# Dual_VCLFO_CTRL.net
KiCad netlist of a schematic drawn in EAGLE
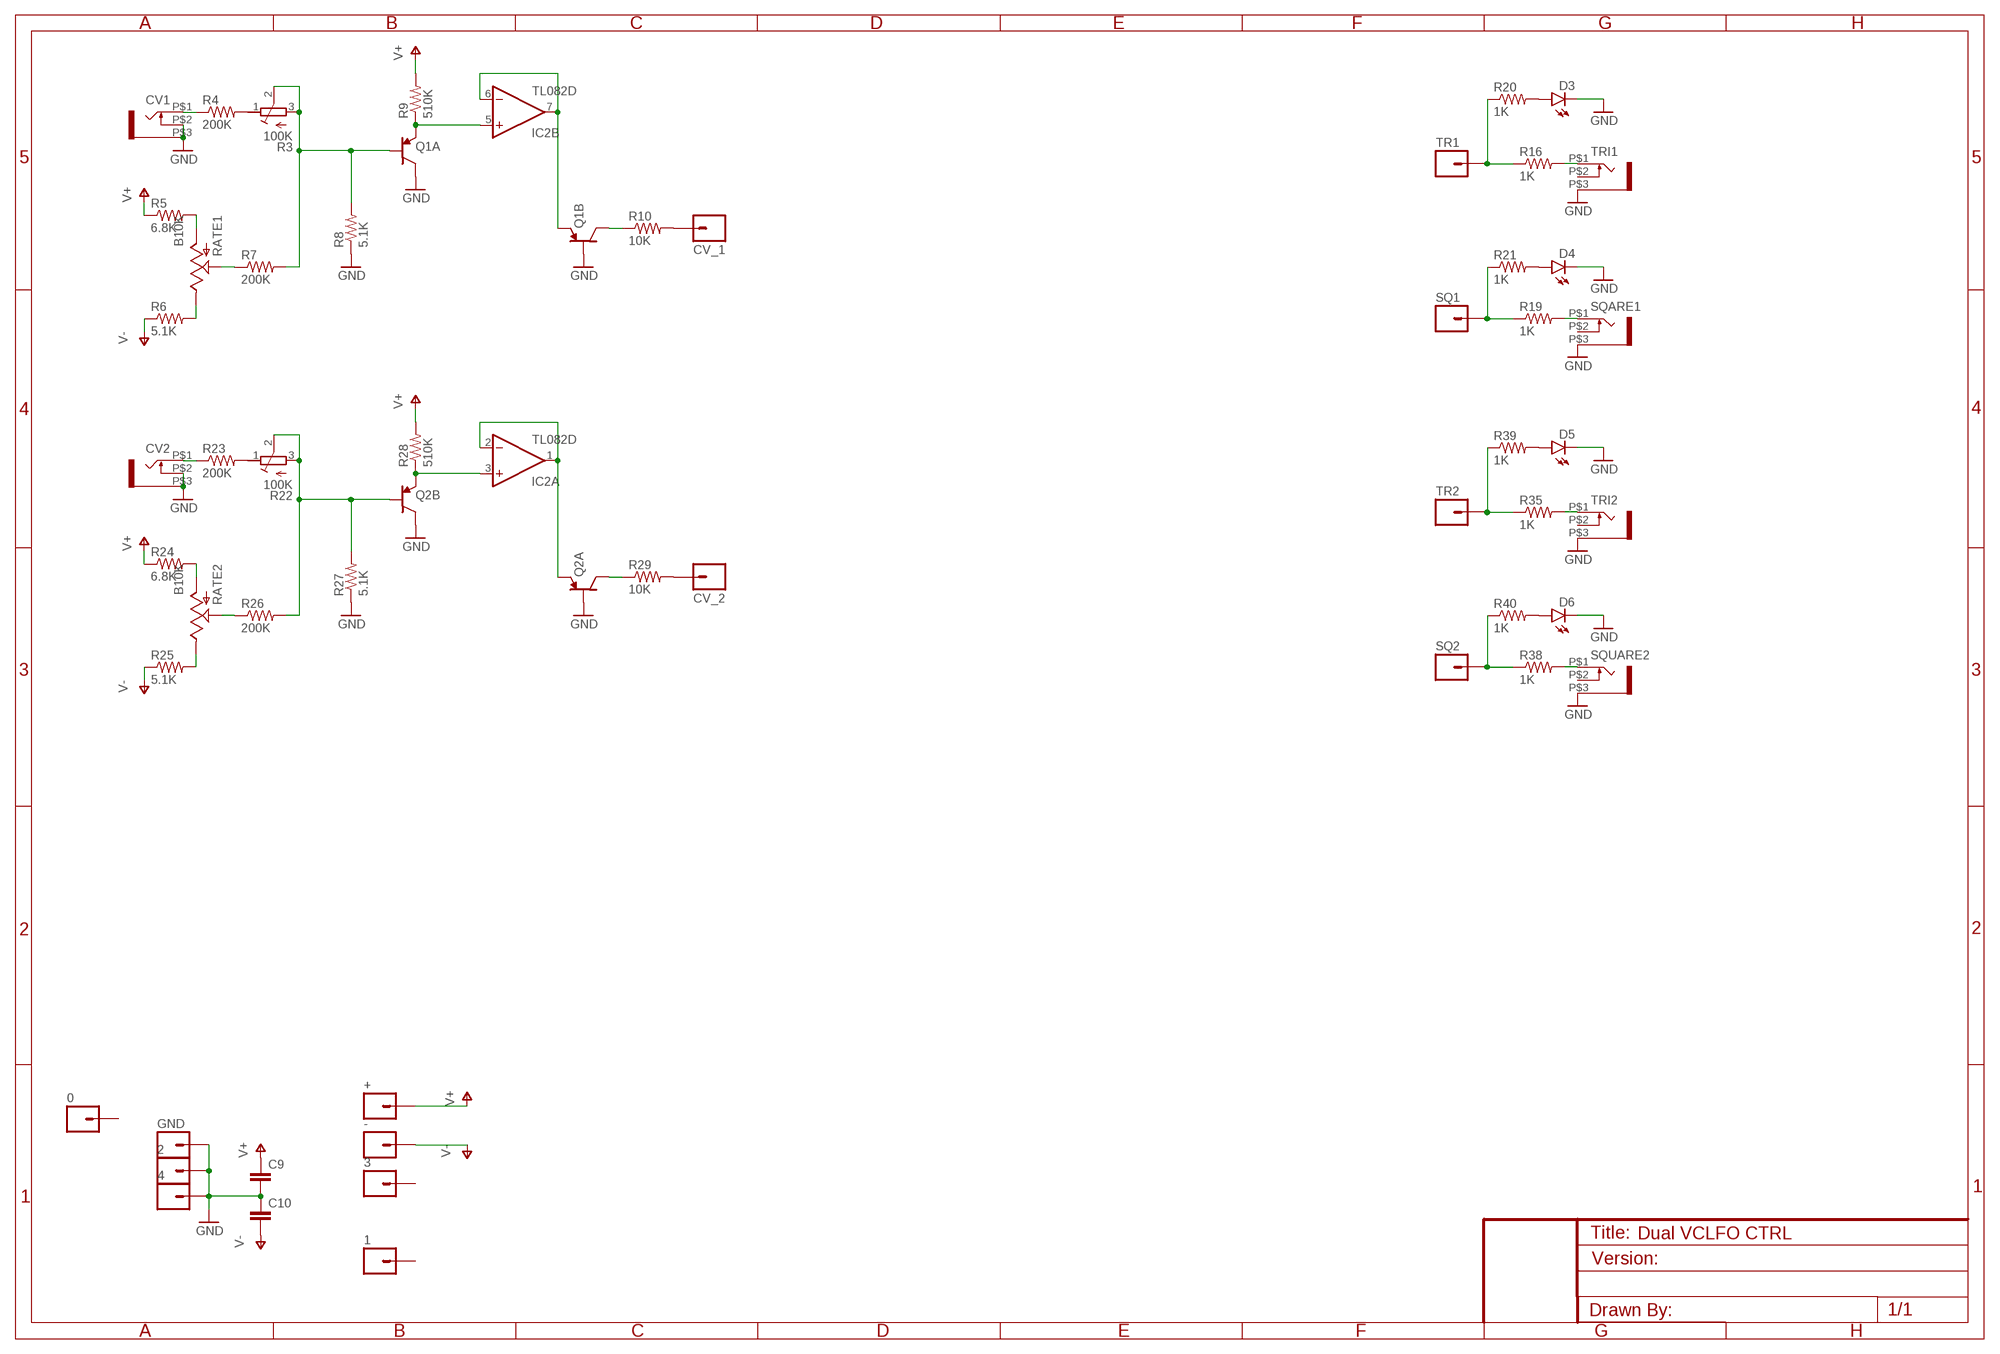
[diagram p0: schematic, sheet 1]

(export (version "E")
  (design (tool "Eeschema 10.0.6"))
  (components
    (comp (ref "+")
      (value "M01PTH")
      (footprint "eagle-import:1X01")
      (libsource (lib "eagle-import") (part "M01PTH"))
    )
    (comp (ref "-")
      (value "M01PTH")
      (footprint "eagle-import:1X01")
      (libsource (lib "eagle-import") (part "M01PTH"))
    )
    (comp (ref "0")
      (value "M01PTH")
      (footprint "eagle-import:1X01")
      (libsource (lib "eagle-import") (part "M01PTH"))
    )
    (comp (ref "1")
      (value "M01PTH")
      (footprint "eagle-import:1X01")
      (libsource (lib "eagle-import") (part "M01PTH"))
    )
    (comp (ref "2")
      (value "M01PTH")
      (footprint "eagle-import:1X01")
      (libsource (lib "eagle-import") (part "M01PTH"))
    )
    (comp (ref "3")
      (value "M01PTH")
      (footprint "eagle-import:1X01")
      (libsource (lib "eagle-import") (part "M01PTH"))
    )
    (comp (ref "4")
      (value "M01PTH")
      (footprint "eagle-import:1X01")
      (libsource (lib "eagle-import") (part "M01PTH"))
    )
    (comp (ref "C9")
      (value "CAP0805")
      (footprint "eagle-import:0805")
      (libsource (lib "eagle-import") (part "CAP0805"))
    )
    (comp (ref "C10")
      (value "CAP0805")
      (footprint "eagle-import:0805")
      (libsource (lib "eagle-import") (part "CAP0805"))
    )
    (comp (ref "CV1")
      (value "WQP-PJ301M-12_JACK")
      (footprint "eagle-import:WQP-PJ301M-12_JACK")
      (libsource (lib "eagle-import") (part "WQP-PJ301M-12_JACK"))
    )
    (comp (ref "CV2")
      (value "WQP-PJ301M-12_JACK")
      (footprint "eagle-import:WQP-PJ301M-12_JACK")
      (libsource (lib "eagle-import") (part "WQP-PJ301M-12_JACK"))
    )
    (comp (ref "CV_1")
      (value "M01PTH")
      (footprint "eagle-import:1X01")
      (libsource (lib "eagle-import") (part "M01PTH"))
    )
    (comp (ref "CV_2")
      (value "M01PTH")
      (footprint "eagle-import:1X01")
      (libsource (lib "eagle-import") (part "M01PTH"))
    )
    (comp (ref "D3")
      (value "LED3MM")
      (footprint "eagle-import:LED3MM")
      (libsource (lib "eagle-import") (part "LED3MM"))
    )
    (comp (ref "D4")
      (value "LED3MM")
      (footprint "eagle-import:LED3MM")
      (libsource (lib "eagle-import") (part "LED3MM"))
    )
    (comp (ref "D5")
      (value "LED3MM")
      (footprint "eagle-import:LED3MM")
      (libsource (lib "eagle-import") (part "LED3MM"))
    )
    (comp (ref "D6")
      (value "LED3MM")
      (footprint "eagle-import:LED3MM")
      (libsource (lib "eagle-import") (part "LED3MM"))
    )
    (comp (ref "GND")
      (value "M01PTH")
      (footprint "eagle-import:1X01")
      (libsource (lib "eagle-import") (part "M01PTH"))
    )
    (comp (ref "IC2")
      (value "TL082D")
      (footprint "eagle-import:SO08")
      (libsource (lib "eagle-import") (part "TL082D"))
    )
    (comp (ref "Q1")
      (value "PNP-DUALPMP5201")
      (footprint "eagle-import:SOT363")
      (libsource (lib "eagle-import") (part "PNP-DUALPMP5201"))
    )
    (comp (ref "Q2")
      (value "PNP-DUALPMP5201")
      (footprint "eagle-import:SOT363")
      (libsource (lib "eagle-import") (part "PNP-DUALPMP5201"))
    )
    (comp (ref "R3")
      (value "100K")
      (footprint "eagle-import:RTRIM3314G")
      (libsource (lib "eagle-import") (part "R-TRIMM3314G"))
    )
    (comp (ref "R4")
      (value "200K")
      (footprint "eagle-import:0805")
      (libsource (lib "eagle-import") (part "RESISTOR0805-RES"))
    )
    (comp (ref "R5")
      (value "6.8K")
      (footprint "eagle-import:0805")
      (libsource (lib "eagle-import") (part "RESISTOR0805-RES"))
    )
    (comp (ref "R6")
      (value "5.1K")
      (footprint "eagle-import:0805")
      (libsource (lib "eagle-import") (part "RESISTOR0805-RES"))
    )
    (comp (ref "R7")
      (value "200K")
      (footprint "eagle-import:0805")
      (libsource (lib "eagle-import") (part "RESISTOR0805-RES"))
    )
    (comp (ref "R8")
      (value "5.1K")
      (footprint "eagle-import:0805")
      (libsource (lib "eagle-import") (part "RESISTOR0805-RES"))
    )
    (comp (ref "R9")
      (value "510K")
      (footprint "eagle-import:0805")
      (libsource (lib "eagle-import") (part "RESISTOR0805-RES"))
    )
    (comp (ref "R10")
      (value "10K")
      (footprint "eagle-import:0805")
      (libsource (lib "eagle-import") (part "RESISTOR0805-RES"))
    )
    (comp (ref "R16")
      (value "1K")
      (footprint "eagle-import:0805")
      (libsource (lib "eagle-import") (part "RESISTOR0805-RES"))
    )
    (comp (ref "R19")
      (value "1K")
      (footprint "eagle-import:0805")
      (libsource (lib "eagle-import") (part "RESISTOR0805-RES"))
    )
    (comp (ref "R20")
      (value "1K")
      (footprint "eagle-import:0805")
      (libsource (lib "eagle-import") (part "RESISTOR0805-RES"))
    )
    (comp (ref "R21")
      (value "1K")
      (footprint "eagle-import:0805")
      (libsource (lib "eagle-import") (part "RESISTOR0805-RES"))
    )
    (comp (ref "R22")
      (value "100K")
      (footprint "eagle-import:RTRIM3314G")
      (libsource (lib "eagle-import") (part "R-TRIMM3314G"))
    )
    (comp (ref "R23")
      (value "200K")
      (footprint "eagle-import:0805")
      (libsource (lib "eagle-import") (part "RESISTOR0805-RES"))
    )
    (comp (ref "R24")
      (value "6.8K")
      (footprint "eagle-import:0805")
      (libsource (lib "eagle-import") (part "RESISTOR0805-RES"))
    )
    (comp (ref "R25")
      (value "5.1K")
      (footprint "eagle-import:0805")
      (libsource (lib "eagle-import") (part "RESISTOR0805-RES"))
    )
    (comp (ref "R26")
      (value "200K")
      (footprint "eagle-import:0805")
      (libsource (lib "eagle-import") (part "RESISTOR0805-RES"))
    )
    (comp (ref "R27")
      (value "5.1K")
      (footprint "eagle-import:0805")
      (libsource (lib "eagle-import") (part "RESISTOR0805-RES"))
    )
    (comp (ref "R28")
      (value "510K")
      (footprint "eagle-import:0805")
      (libsource (lib "eagle-import") (part "RESISTOR0805-RES"))
    )
    (comp (ref "R29")
      (value "10K")
      (footprint "eagle-import:0805")
      (libsource (lib "eagle-import") (part "RESISTOR0805-RES"))
    )
    (comp (ref "R35")
      (value "1K")
      (footprint "eagle-import:0805")
      (libsource (lib "eagle-import") (part "RESISTOR0805-RES"))
    )
    (comp (ref "R38")
      (value "1K")
      (footprint "eagle-import:0805")
      (libsource (lib "eagle-import") (part "RESISTOR0805-RES"))
    )
    (comp (ref "R39")
      (value "1K")
      (footprint "eagle-import:0805")
      (libsource (lib "eagle-import") (part "RESISTOR0805-RES"))
    )
    (comp (ref "R40")
      (value "1K")
      (footprint "eagle-import:0805")
      (libsource (lib "eagle-import") (part "RESISTOR0805-RES"))
    )
    (comp (ref "RATE1")
      (value "B10K")
      (footprint "eagle-import:ALPS_POT")
      (libsource (lib "eagle-import") (part "POT"))
    )
    (comp (ref "RATE2")
      (value "B10K")
      (footprint "eagle-import:ALPS_POT")
      (libsource (lib "eagle-import") (part "POT"))
    )
    (comp (ref "SQ1")
      (value "M01PTH")
      (footprint "eagle-import:1X01")
      (libsource (lib "eagle-import") (part "M01PTH"))
    )
    (comp (ref "SQ2")
      (value "M01PTH")
      (footprint "eagle-import:1X01")
      (libsource (lib "eagle-import") (part "M01PTH"))
    )
    (comp (ref "SQARE1")
      (value "WQP-PJ301M-12_JACK")
      (footprint "eagle-import:WQP-PJ301M-12_JACK")
      (libsource (lib "eagle-import") (part "WQP-PJ301M-12_JACK"))
    )
    (comp (ref "SQUARE2")
      (value "WQP-PJ301M-12_JACK")
      (footprint "eagle-import:WQP-PJ301M-12_JACK")
      (libsource (lib "eagle-import") (part "WQP-PJ301M-12_JACK"))
    )
    (comp (ref "TR1")
      (value "M01PTH")
      (footprint "eagle-import:1X01")
      (libsource (lib "eagle-import") (part "M01PTH"))
    )
    (comp (ref "TR2")
      (value "M01PTH")
      (footprint "eagle-import:1X01")
      (libsource (lib "eagle-import") (part "M01PTH"))
    )
    (comp (ref "TRI1")
      (value "WQP-PJ301M-12_JACK")
      (footprint "eagle-import:WQP-PJ301M-12_JACK")
      (libsource (lib "eagle-import") (part "WQP-PJ301M-12_JACK"))
    )
    (comp (ref "TRI2")
      (value "WQP-PJ301M-12_JACK")
      (footprint "eagle-import:WQP-PJ301M-12_JACK")
      (libsource (lib "eagle-import") (part "WQP-PJ301M-12_JACK"))
    )
  )
  (nets
    (net (code "1") (name "GND") (class "Default")
      (node (ref "2") (pin "1") (pinfunction "1_1") (pintype "passive"))
      (node (ref "4") (pin "1") (pinfunction "1_1") (pintype "passive"))
      (node (ref "C10") (pin "1") (pinfunction "1_1") (pintype "passive"))
      (node (ref "C9") (pin "2") (pinfunction "2_2") (pintype "passive"))
      (node (ref "CV1") (pin "P$2") (pinfunction "3_P$2") (pintype "passive"))
      (node (ref "CV1") (pin "P$3") (pinfunction "1_P$3") (pintype "passive"))
      (node (ref "CV2") (pin "P$2") (pinfunction "3_P$2") (pintype "passive"))
      (node (ref "CV2") (pin "P$3") (pinfunction "1_P$3") (pintype "passive"))
      (node (ref "D3") (pin "K") (pinfunction "C_K") (pintype "passive"))
      (node (ref "D4") (pin "K") (pinfunction "C_K") (pintype "passive"))
      (node (ref "D5") (pin "K") (pinfunction "C_K") (pintype "passive"))
      (node (ref "D6") (pin "K") (pinfunction "C_K") (pintype "passive"))
      (node (ref "GND") (pin "1") (pinfunction "1_1") (pintype "passive"))
      (node (ref "Q1") (pin "P$2") (pinfunction "P$1_P$2") (pintype "bidirectional"))
      (node (ref "Q1") (pin "P$6") (pinfunction "P$3_P$6") (pintype "bidirectional"))
      (node (ref "Q2") (pin "P$1") (pinfunction "P$1_P$1") (pintype "bidirectional"))
      (node (ref "Q2") (pin "P$3") (pinfunction "P$3_P$3") (pintype "bidirectional"))
      (node (ref "R27") (pin "1") (pinfunction "1_1") (pintype "passive"))
      (node (ref "R8") (pin "1") (pinfunction "1_1") (pintype "passive"))
      (node (ref "SQARE1") (pin "P$3") (pinfunction "1_P$3") (pintype "passive"))
      (node (ref "SQUARE2") (pin "P$3") (pinfunction "1_P$3") (pintype "passive"))
      (node (ref "TRI1") (pin "P$3") (pinfunction "1_P$3") (pintype "passive"))
      (node (ref "TRI2") (pin "P$3") (pinfunction "1_P$3") (pintype "passive"))
    )
    (net (code "2") (name "Net-(CV1-2)") (class "Default")
      (node (ref "CV1") (pin "P$1") (pinfunction "2_P$1") (pintype "passive"))
      (node (ref "R4") (pin "1") (pinfunction "1_1") (pintype "passive"))
    )
    (net (code "3") (name "Net-(CV2-2)") (class "Default")
      (node (ref "CV2") (pin "P$1") (pinfunction "2_P$1") (pintype "passive"))
      (node (ref "R23") (pin "1") (pinfunction "1_1") (pintype "passive"))
    )
    (net (code "4") (name "Net-(CV_1-Pad1)") (class "Default")
      (node (ref "CV_1") (pin "1") (pinfunction "1_1") (pintype "passive"))
      (node (ref "R10") (pin "2") (pinfunction "2_2") (pintype "passive"))
    )
    (net (code "5") (name "Net-(CV_2-Pad1)") (class "Default")
      (node (ref "CV_2") (pin "1") (pinfunction "1_1") (pintype "passive"))
      (node (ref "R29") (pin "2") (pinfunction "2_2") (pintype "passive"))
    )
    (net (code "6") (name "Net-(D3-PadA)") (class "Default")
      (node (ref "D3") (pin "A") (pinfunction "A_A") (pintype "passive"))
      (node (ref "R20") (pin "2") (pinfunction "2_2") (pintype "passive"))
    )
    (net (code "7") (name "Net-(D4-PadA)") (class "Default")
      (node (ref "D4") (pin "A") (pinfunction "A_A") (pintype "passive"))
      (node (ref "R21") (pin "2") (pinfunction "2_2") (pintype "passive"))
    )
    (net (code "8") (name "Net-(D5-PadA)") (class "Default")
      (node (ref "D5") (pin "A") (pinfunction "A_A") (pintype "passive"))
      (node (ref "R39") (pin "2") (pinfunction "2_2") (pintype "passive"))
    )
    (net (code "9") (name "Net-(D6-PadA)") (class "Default")
      (node (ref "D6") (pin "A") (pinfunction "A_A") (pintype "passive"))
      (node (ref "R40") (pin "2") (pinfunction "2_2") (pintype "passive"))
    )
    (net (code "10") (name "Net-(IC2A-+IN)") (class "Default")
      (node (ref "IC2") (pin "3") (pinfunction "+IN_3") (pintype "input"))
      (node (ref "Q2") (pin "P$4") (pinfunction "P$2_P$4") (pintype "bidirectional"))
      (node (ref "R28") (pin "1") (pinfunction "1_1") (pintype "passive"))
    )
    (net (code "11") (name "Net-(IC2A--IN)") (class "Default")
      (node (ref "IC2") (pin "1") (pinfunction "OUT_1") (pintype "output"))
      (node (ref "IC2") (pin "2") (pinfunction "-IN_2") (pintype "input"))
      (node (ref "Q2") (pin "P$5") (pinfunction "P$2_P$5") (pintype "bidirectional"))
    )
    (net (code "12") (name "Net-(IC2B-+IN)") (class "Default")
      (node (ref "IC2") (pin "5") (pinfunction "+IN_5") (pintype "input"))
      (node (ref "Q1") (pin "P$5") (pinfunction "P$2_P$5") (pintype "bidirectional"))
      (node (ref "R9") (pin "1") (pinfunction "1_1") (pintype "passive"))
    )
    (net (code "13") (name "Net-(IC2B--IN)") (class "Default")
      (node (ref "IC2") (pin "6") (pinfunction "-IN_6") (pintype "input"))
      (node (ref "IC2") (pin "7") (pinfunction "OUT_7") (pintype "output"))
      (node (ref "Q1") (pin "P$4") (pinfunction "P$2_P$4") (pintype "bidirectional"))
    )
    (net (code "14") (name "Net-(Q1-PadP$3)") (class "Default")
      (node (ref "Q1") (pin "P$3") (pinfunction "P$3_P$3") (pintype "bidirectional"))
      (node (ref "R10") (pin "1") (pinfunction "1_1") (pintype "passive"))
    )
    (net (code "15") (name "Net-(Q2A-P$3)") (class "Default")
      (node (ref "Q2") (pin "P$6") (pinfunction "P$3_P$6") (pintype "bidirectional"))
      (node (ref "R29") (pin "1") (pinfunction "1_1") (pintype "passive"))
    )
    (net (code "16") (name "Net-(Q2B-P$1)") (class "Default")
      (node (ref "Q2") (pin "P$2") (pinfunction "P$1_P$2") (pintype "bidirectional"))
      (node (ref "R22") (pin "2") (pinfunction "S_2") (pintype "passive"))
      (node (ref "R22") (pin "3") (pinfunction "A_3") (pintype "passive"))
      (node (ref "R26") (pin "2") (pinfunction "2_2") (pintype "passive"))
      (node (ref "R27") (pin "2") (pinfunction "2_2") (pintype "passive"))
    )
    (net (code "17") (name "Net-(R3-A)") (class "Default")
      (node (ref "Q1") (pin "P$1") (pinfunction "P$1_P$1") (pintype "bidirectional"))
      (node (ref "R3") (pin "2") (pinfunction "S_2") (pintype "passive"))
      (node (ref "R3") (pin "3") (pinfunction "A_3") (pintype "passive"))
      (node (ref "R7") (pin "2") (pinfunction "2_2") (pintype "passive"))
      (node (ref "R8") (pin "2") (pinfunction "2_2") (pintype "passive"))
    )
    (net (code "18") (name "Net-(R3-E)") (class "Default")
      (node (ref "R3") (pin "1") (pinfunction "E_1") (pintype "passive"))
      (node (ref "R4") (pin "2") (pinfunction "2_2") (pintype "passive"))
    )
    (net (code "19") (name "Net-(R16-Pad1)") (class "Default")
      (node (ref "R16") (pin "1") (pinfunction "1_1") (pintype "passive"))
      (node (ref "R20") (pin "1") (pinfunction "1_1") (pintype "passive"))
      (node (ref "TR1") (pin "1") (pinfunction "1_1") (pintype "passive"))
    )
    (net (code "20") (name "Net-(R19-Pad1)") (class "Default")
      (node (ref "R19") (pin "1") (pinfunction "1_1") (pintype "passive"))
      (node (ref "R21") (pin "1") (pinfunction "1_1") (pintype "passive"))
      (node (ref "SQ1") (pin "1") (pinfunction "1_1") (pintype "passive"))
    )
    (net (code "21") (name "Net-(R22-E)") (class "Default")
      (node (ref "R22") (pin "1") (pinfunction "E_1") (pintype "passive"))
      (node (ref "R23") (pin "2") (pinfunction "2_2") (pintype "passive"))
    )
    (net (code "22") (name "Net-(R35-Pad1)") (class "Default")
      (node (ref "R35") (pin "1") (pinfunction "1_1") (pintype "passive"))
      (node (ref "R39") (pin "1") (pinfunction "1_1") (pintype "passive"))
      (node (ref "TR2") (pin "1") (pinfunction "1_1") (pintype "passive"))
    )
    (net (code "23") (name "Net-(R38-Pad1)") (class "Default")
      (node (ref "R38") (pin "1") (pinfunction "1_1") (pintype "passive"))
      (node (ref "R40") (pin "1") (pinfunction "1_1") (pintype "passive"))
      (node (ref "SQ2") (pin "1") (pinfunction "1_1") (pintype "passive"))
    )
    (net (code "24") (name "Net-(RATE1-A)") (class "Default")
      (node (ref "R5") (pin "2") (pinfunction "2_2") (pintype "passive"))
      (node (ref "RATE1") (pin "P$3") (pinfunction "A_P$3") (pintype "passive"))
    )
    (net (code "25") (name "Net-(RATE1-E)") (class "Default")
      (node (ref "R6") (pin "2") (pinfunction "2_2") (pintype "passive"))
      (node (ref "RATE1") (pin "P$1") (pinfunction "E_P$1") (pintype "passive"))
    )
    (net (code "26") (name "Net-(RATE1-S)") (class "Default")
      (node (ref "R7") (pin "1") (pinfunction "1_1") (pintype "passive"))
      (node (ref "RATE1") (pin "P$2") (pinfunction "S_P$2") (pintype "passive"))
    )
    (net (code "27") (name "Net-(RATE2-A)") (class "Default")
      (node (ref "R24") (pin "2") (pinfunction "2_2") (pintype "passive"))
      (node (ref "RATE2") (pin "P$3") (pinfunction "A_P$3") (pintype "passive"))
    )
    (net (code "28") (name "Net-(RATE2-E)") (class "Default")
      (node (ref "R25") (pin "2") (pinfunction "2_2") (pintype "passive"))
      (node (ref "RATE2") (pin "P$1") (pinfunction "E_P$1") (pintype "passive"))
    )
    (net (code "29") (name "Net-(RATE2-S)") (class "Default")
      (node (ref "R26") (pin "1") (pinfunction "1_1") (pintype "passive"))
      (node (ref "RATE2") (pin "P$2") (pinfunction "S_P$2") (pintype "passive"))
    )
    (net (code "30") (name "Net-(SQARE1-2)") (class "Default")
      (node (ref "R19") (pin "2") (pinfunction "2_2") (pintype "passive"))
      (node (ref "SQARE1") (pin "P$1") (pinfunction "2_P$1") (pintype "passive"))
    )
    (net (code "31") (name "Net-(SQUARE2-2)") (class "Default")
      (node (ref "R38") (pin "2") (pinfunction "2_2") (pintype "passive"))
      (node (ref "SQUARE2") (pin "P$1") (pinfunction "2_P$1") (pintype "passive"))
    )
    (net (code "32") (name "Net-(TRI1-2)") (class "Default")
      (node (ref "R16") (pin "2") (pinfunction "2_2") (pintype "passive"))
      (node (ref "TRI1") (pin "P$1") (pinfunction "2_P$1") (pintype "passive"))
    )
    (net (code "33") (name "Net-(TRI2-2)") (class "Default")
      (node (ref "R35") (pin "2") (pinfunction "2_2") (pintype "passive"))
      (node (ref "TRI2") (pin "P$1") (pinfunction "2_P$1") (pintype "passive"))
    )
    (net (code "34") (name "V+") (class "Default")
      (node (ref "+") (pin "1") (pinfunction "1_1") (pintype "passive"))
      (node (ref "C9") (pin "1") (pinfunction "1_1") (pintype "passive"))
      (node (ref "R24") (pin "1") (pinfunction "1_1") (pintype "passive"))
      (node (ref "R28") (pin "2") (pinfunction "2_2") (pintype "passive"))
      (node (ref "R5") (pin "1") (pinfunction "1_1") (pintype "passive"))
      (node (ref "R9") (pin "2") (pinfunction "2_2") (pintype "passive"))
    )
    (net (code "35") (name "V-") (class "Default")
      (node (ref "-") (pin "1") (pinfunction "1_1") (pintype "passive"))
      (node (ref "C10") (pin "2") (pinfunction "2_2") (pintype "passive"))
      (node (ref "R25") (pin "1") (pinfunction "1_1") (pintype "passive"))
      (node (ref "R6") (pin "1") (pinfunction "1_1") (pintype "passive"))
    )
    (net (code "36") (name "unconnected-(0-Pad1)") (class "Default")
      (node (ref "0") (pin "1") (pinfunction "1_1") (pintype "passive"))
    )
    (net (code "37") (name "unconnected-(1-Pad1)") (class "Default")
      (node (ref "1") (pin "1") (pinfunction "1_1") (pintype "passive"))
    )
    (net (code "38") (name "unconnected-(3-Pad1)") (class "Default")
      (node (ref "3") (pin "1") (pinfunction "1_1") (pintype "passive"))
    )
    (net (code "39") (name "unconnected-(SQARE1-3-PadP$2)") (class "Default")
      (node (ref "SQARE1") (pin "P$2") (pinfunction "3_P$2") (pintype "passive"))
    )
    (net (code "40") (name "unconnected-(SQUARE2-3-PadP$2)") (class "Default")
      (node (ref "SQUARE2") (pin "P$2") (pinfunction "3_P$2") (pintype "passive"))
    )
    (net (code "41") (name "unconnected-(TRI1-3-PadP$2)") (class "Default")
      (node (ref "TRI1") (pin "P$2") (pinfunction "3_P$2") (pintype "passive"))
    )
    (net (code "42") (name "unconnected-(TRI2-3-PadP$2)") (class "Default")
      (node (ref "TRI2") (pin "P$2") (pinfunction "3_P$2") (pintype "passive"))
    )
  )
)
